# Pressure_Sensor2.net
KiCad netlist of a schematic drawn in EasyEDA
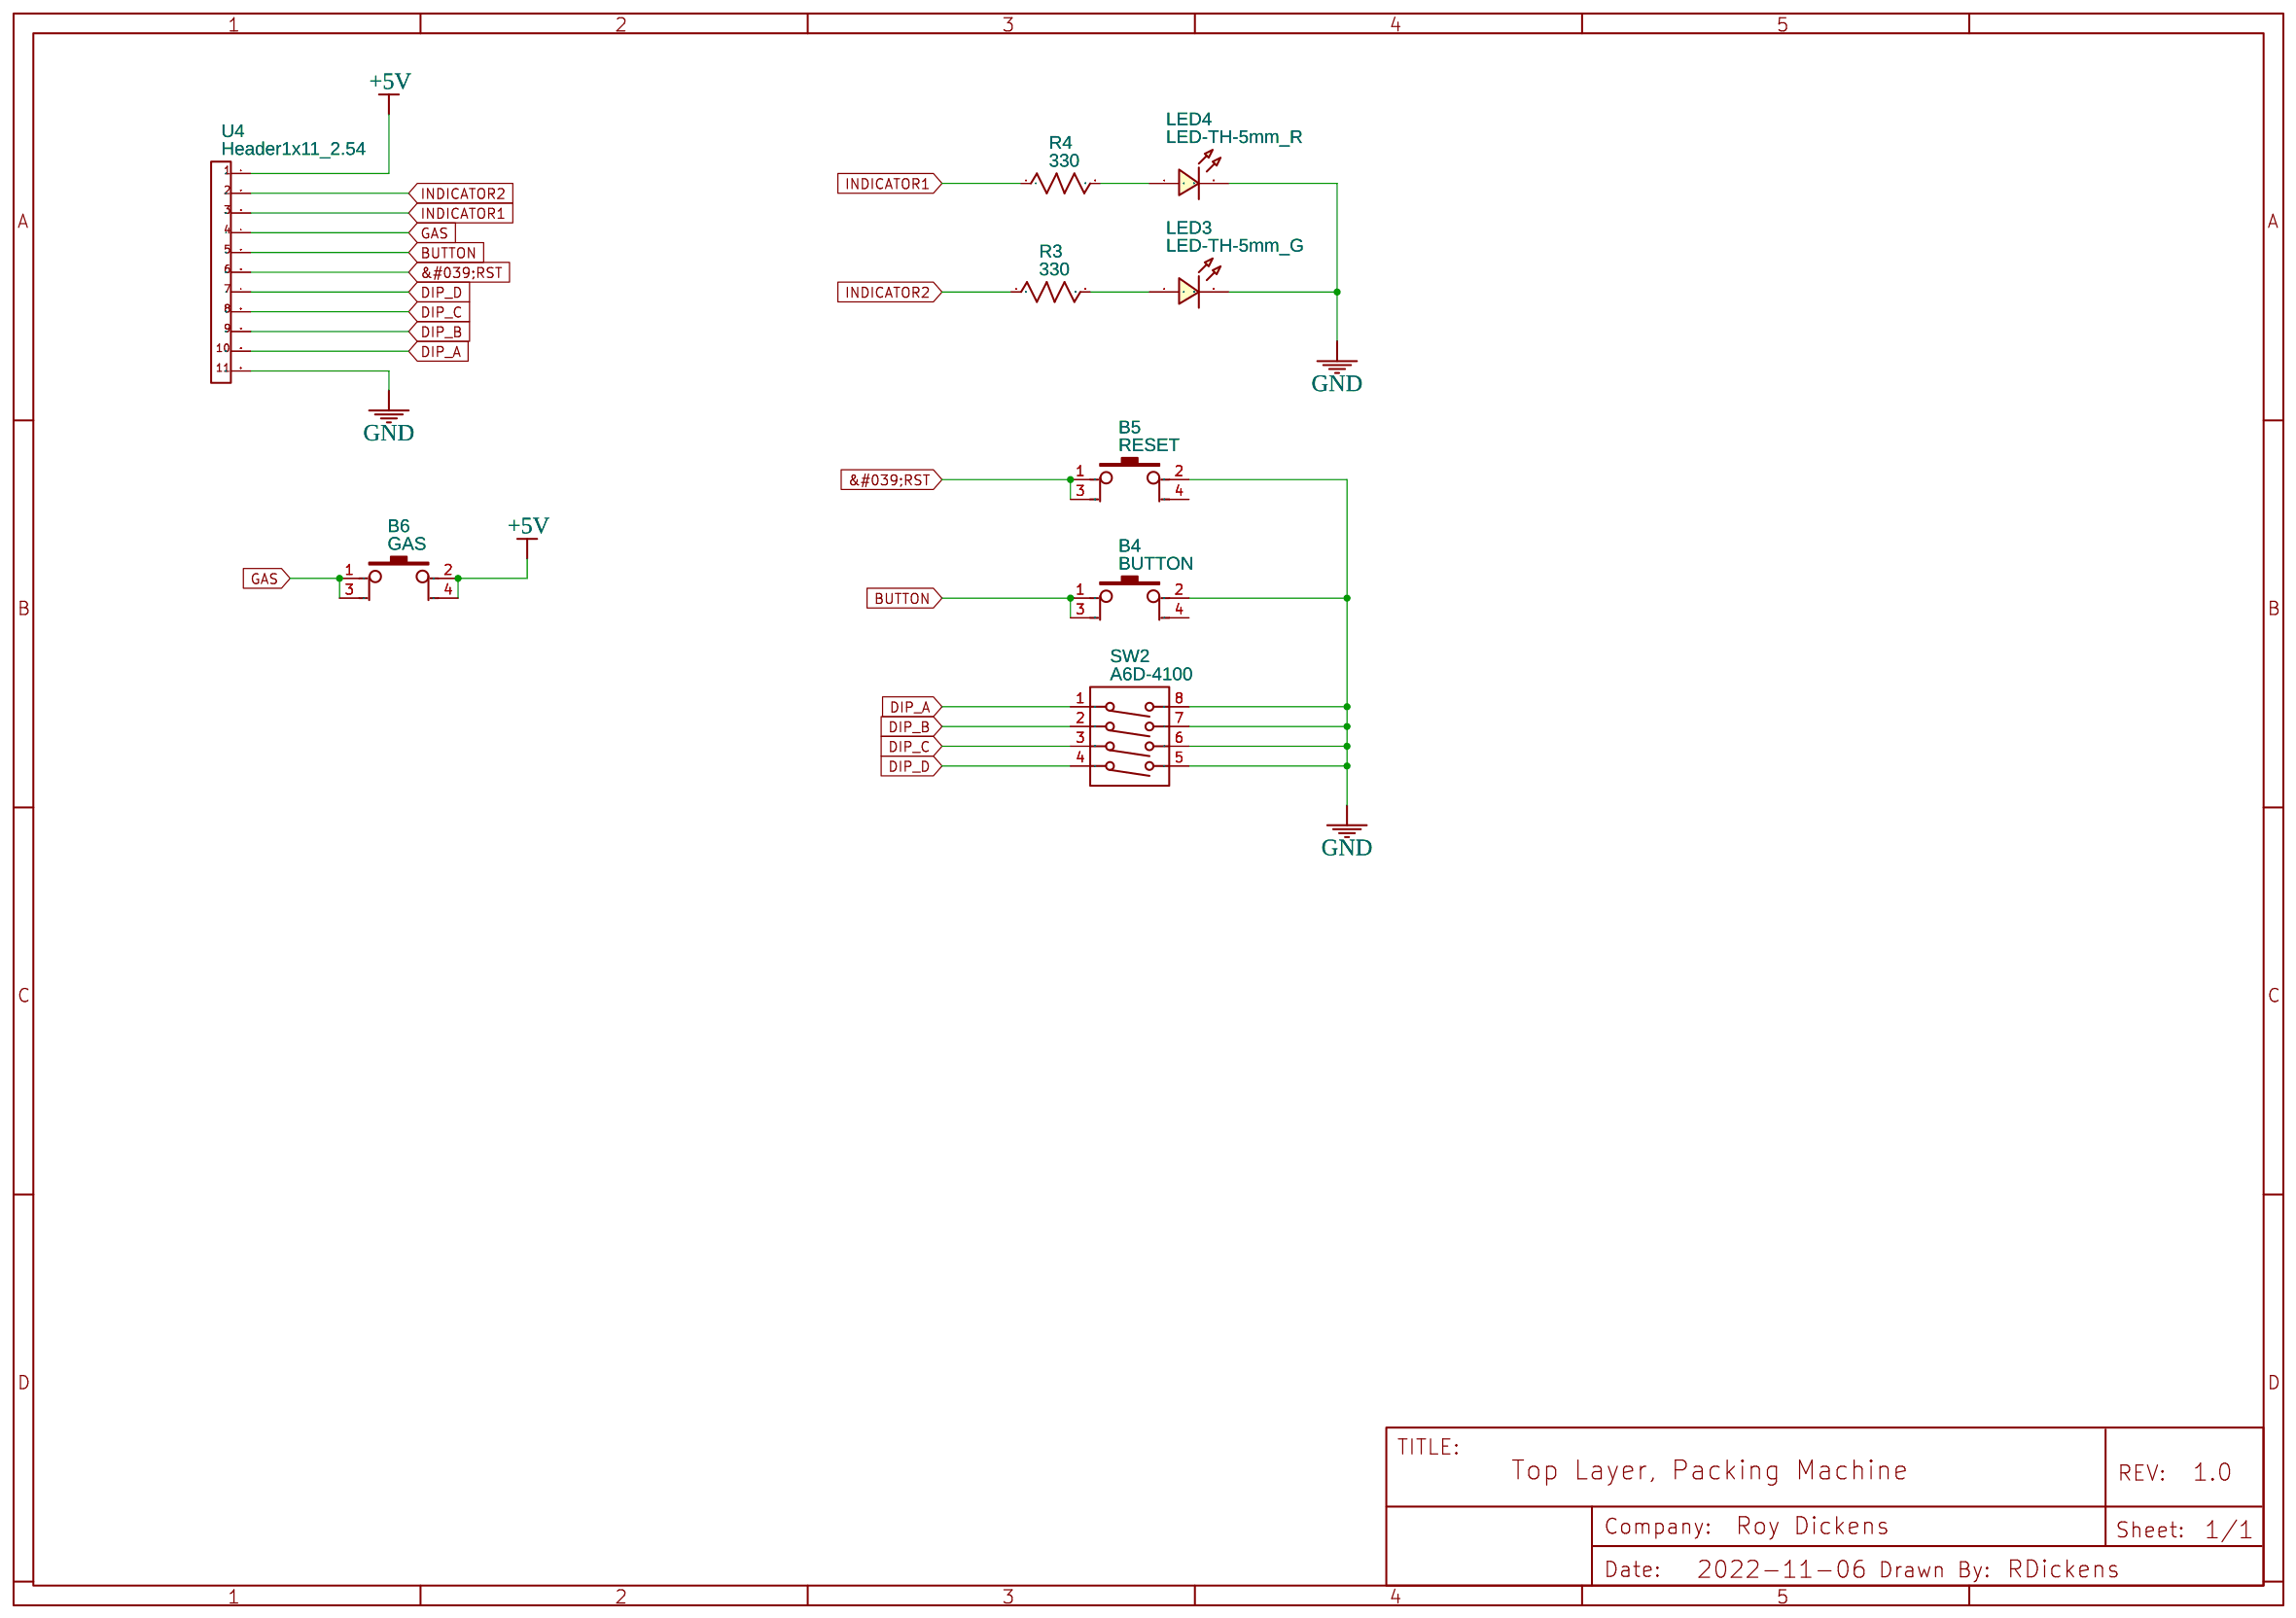
[diagram p0: Sheet_2]
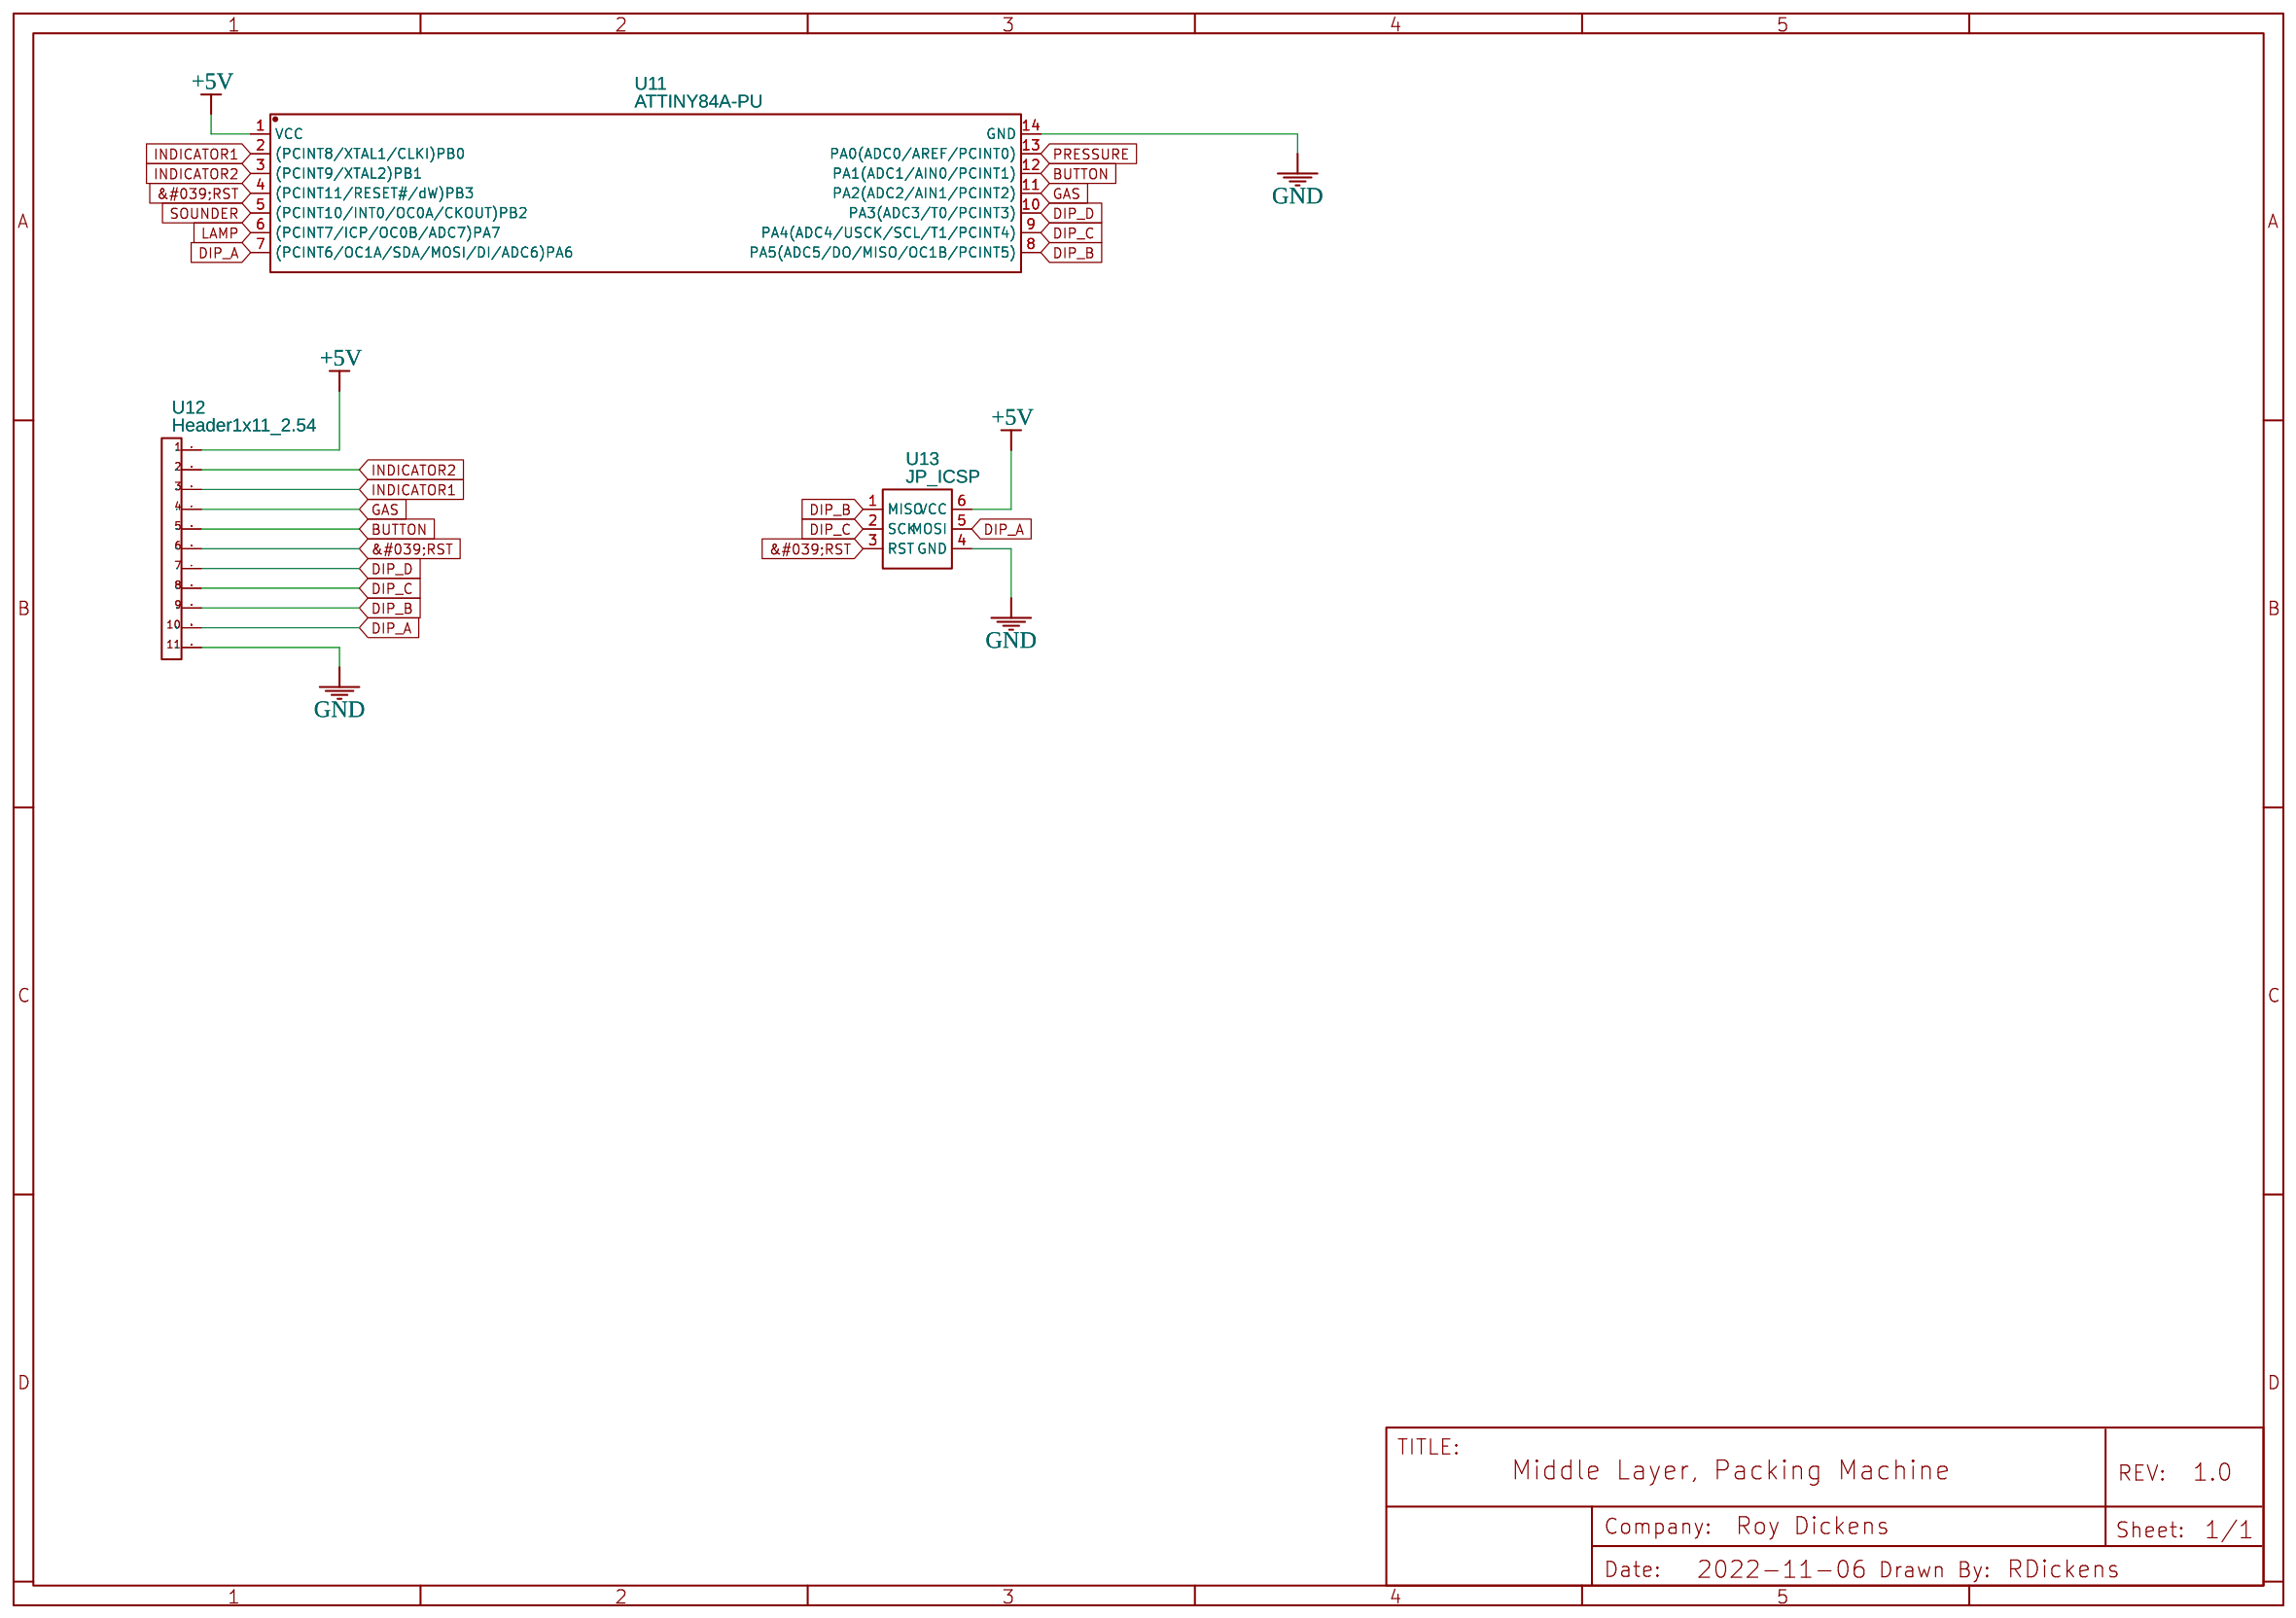
[diagram p1: Sheet_3]
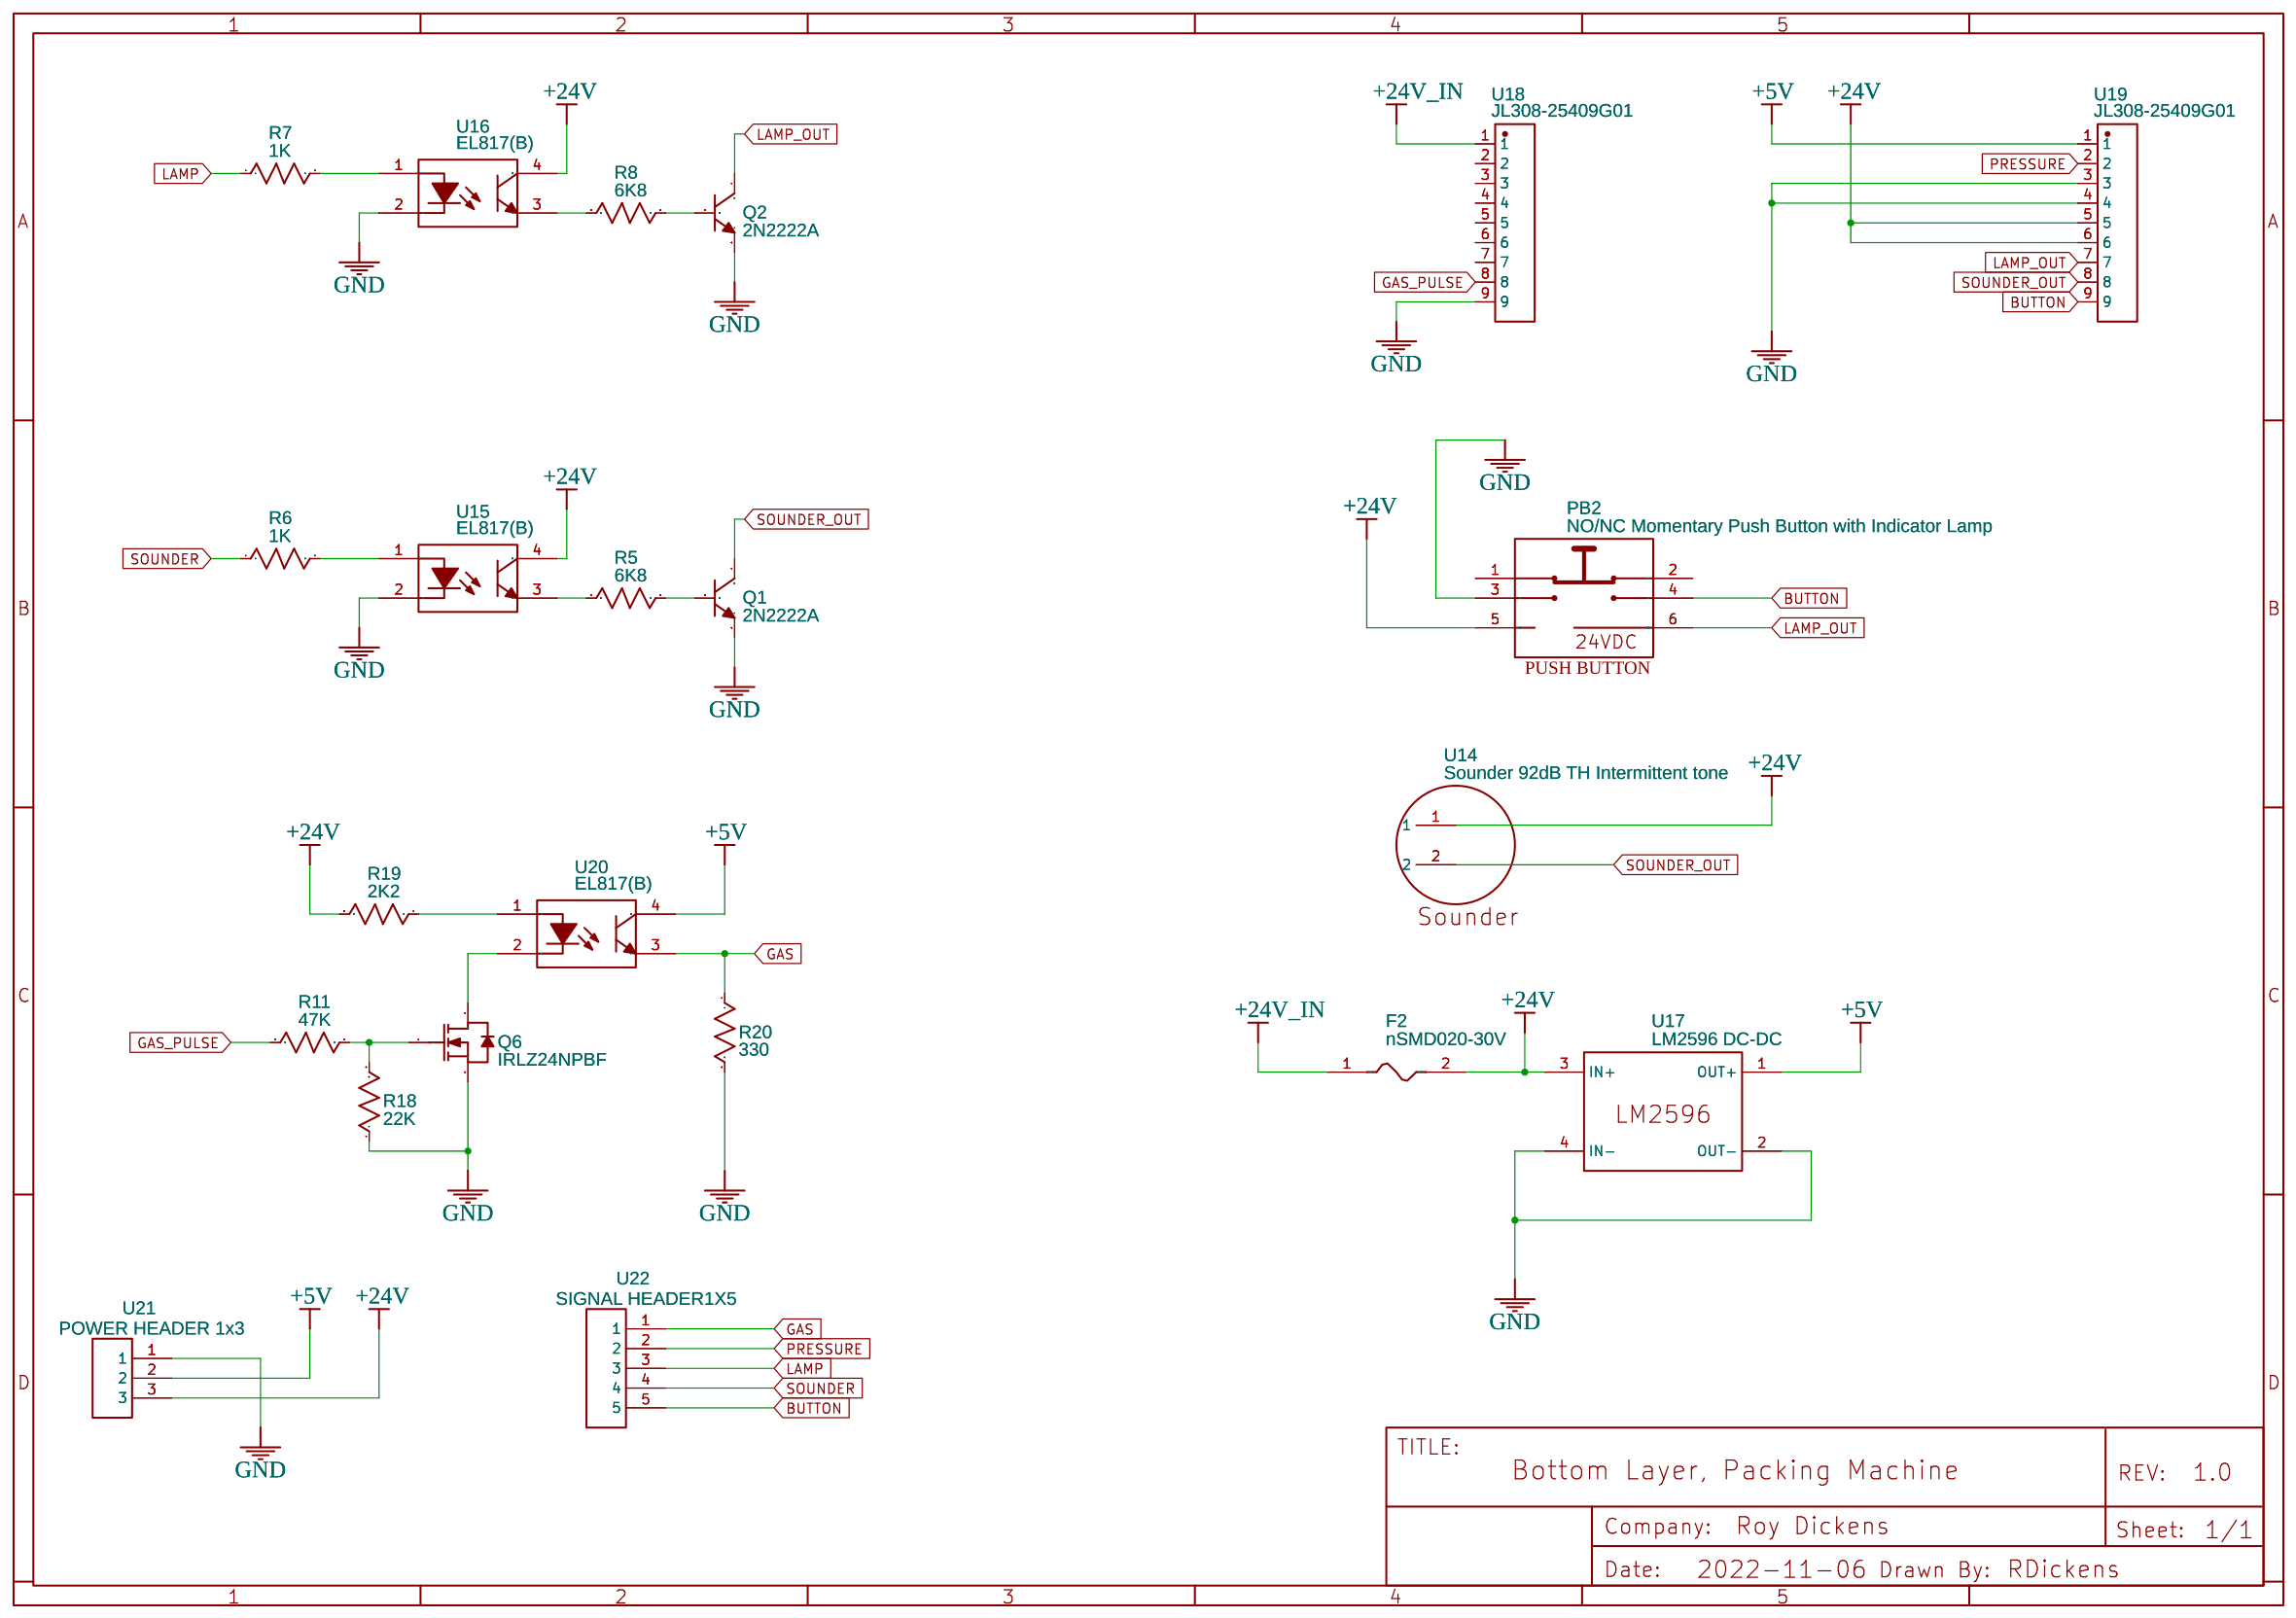
[diagram p2: Sheet_4]

(export (version "E")
  (design (tool "Eeschema 10.0.6"))
  (components
    (comp (ref "B4")
      (value "BUTTON")
      (fields
        (field (name "BOM_Manufacturer Part") "K2-1109DF-F4SW-04")
        (field (name "BOM_Supplier Part") "C2909685")
      )
      (libsource (lib "") (part "PUSHBUTTON"))
    )
    (comp (ref "B5")
      (value "RESET")
      (fields
        (field (name "BOM_Manufacturer Part") "K2-1109DF-F4SW-04")
        (field (name "BOM_Supplier Part") "C2909685")
      )
      (libsource (lib "") (part "PUSHBUTTON"))
    )
    (comp (ref "B6")
      (value "GAS")
      (fields
        (field (name "BOM_Manufacturer Part") "K2-1109DF-F4SW-04")
        (field (name "BOM_Supplier Part") "C2909685")
      )
      (libsource (lib "") (part "PUSHBUTTON"))
    )
    (comp (ref "LED3")
      (value "LED-TH-5mm_G")
      (fields
        (field (name "BOM_Manufacturer Part") "333-2SURD/S530-A3")
        (field (name "BOM_Supplier Part") "C87271")
      )
      (libsource (lib "") (part "LED-TH-5mm_R"))
    )
    (comp (ref "LED4")
      (value "LED-TH-5mm_R")
      (fields
        (field (name "BOM_Manufacturer Part") "333-2SURD/S530-A3")
        (field (name "BOM_Supplier Part") "C87271")
      )
      (libsource (lib "") (part "LED-TH-5mm_R"))
    )
    (comp (ref "R3")
      (value "330")
      (fields
        (field (name "BOM_Manufacturer Part") "MF1/4W-330Ω±1%T52")
        (field (name "BOM_Supplier Part") "C713986")
      )
      (libsource (lib "") (part "R_0603_US"))
    )
    (comp (ref "R4")
      (value "330")
      (fields
        (field (name "BOM_Manufacturer Part") "MF1/4W-330Ω±1%T52")
        (field (name "BOM_Supplier Part") "C713986")
      )
      (libsource (lib "") (part "R_0603_US"))
    )
    (comp (ref "SW2")
      (value "A6D-4100")
      (fields (field (name "BOM_Supplier Part") "C3313543"))
      (libsource (lib "") (part "A6D-4100"))
    )
    (comp (ref "U4") (value "Header1x11_2.54") (libsource (lib "") (part "Header1x11_2.54")))
    (comp (ref "U11")
      (value "ATTINY84A-PU")
      (fields (field (name "BOM_Supplier Part") "C145560"))
      (libsource (lib "") (part "ATTINY84A-PU"))
    )
    (comp (ref "U12") (value "Header1x11_2.54") (libsource (lib "") (part "Header1x11_2.54")))
    (comp (ref "U13")
      (value "JP_ICSP")
      (fields
        (field (name "BOM_Manufacturer Part") "321006SG0ABK00A01")
        (field (name "BOM_Supplier Part") "C601936")
      )
      (libsource (lib "") (part "JP_ICSP"))
    )
    (comp (ref "F2")
      (value "nSMD020-30V")
      (fields (field (name "BOM_Supplier Part") "C69680"))
      (libsource (lib "") (part "nSMD020-30V"))
    )
    (comp (ref "PB2")
      (value "NO/NC Momentary Push Button with Indicator Lamp")
      (libsource (lib "") (part "NO/NC Momentary Push Button with Indicator Lamp"))
    )
    (comp (ref "Q1")
      (value "2N2222A")
      (fields (field (name "BOM_Supplier Part") "C358533"))
      (libsource (lib "") (part "2N2222A"))
    )
    (comp (ref "Q2")
      (value "2N2222A")
      (fields (field (name "BOM_Supplier Part") "C358533"))
      (libsource (lib "") (part "2N2222A"))
    )
    (comp (ref "Q6")
      (value "IRLZ24NPBF")
      (fields (field (name "BOM_Supplier Part") "C11733"))
      (libsource (lib "") (part "IRLZ24NPBF"))
    )
    (comp (ref "R5")
      (value "6K8")
      (fields (field (name "BOM_Supplier Part") "C119314"))
      (libsource (lib "") (part "R_0603_US_1"))
    )
    (comp (ref "R6")
      (value "1K")
      (fields (field (name "BOM_Supplier Part") "C119314"))
      (libsource (lib "") (part "R_0603_US"))
    )
    (comp (ref "R7")
      (value "1K")
      (fields (field (name "BOM_Supplier Part") "C119314"))
      (libsource (lib "") (part "R_0603_US"))
    )
    (comp (ref "R8")
      (value "6K8")
      (fields (field (name "BOM_Supplier Part") "C119314"))
      (libsource (lib "") (part "R_0603_US_1"))
    )
    (comp (ref "R11")
      (value "47K")
      (fields
        (field (name "BOM_Manufacturer Part") "MF1/4W-24KΩ±1%T52")
        (field (name "BOM_Supplier Part") "C714023")
      )
      (libsource (lib "") (part "R_0603_US"))
    )
    (comp (ref "R18")
      (value "22K")
      (fields
        (field (name "BOM_Manufacturer Part") "MF1/4W-24KΩ±1%T52")
        (field (name "BOM_Supplier Part") "C714023")
      )
      (libsource (lib "") (part "R_0603_US_3"))
    )
    (comp (ref "R19")
      (value "2K2")
      (fields
        (field (name "BOM_Manufacturer Part") "MF1/4W-2.2KΩ±1%T52")
        (field (name "BOM_Supplier Part") "C714002")
      )
      (libsource (lib "") (part "R_0603_US_1"))
    )
    (comp (ref "R20")
      (value "330")
      (fields (field (name "BOM_Supplier Part") "C119314"))
      (libsource (lib "") (part "R_0603_US_2"))
    )
    (comp (ref "U14")
      (value "Sounder 92dB TH Intermittent tone")
      (fields (field (name "BOM_Supplier Part") "172-7560"))
      (libsource (lib "") (part "Sounder 92dB TH Intermittent tone"))
    )
    (comp (ref "U15")
      (value "EL817(B)")
      (fields (field (name "BOM_Supplier Part") "C4749156"))
      (libsource (lib "") (part "EL817(B)"))
    )
    (comp (ref "U16")
      (value "EL817(B)")
      (fields (field (name "BOM_Supplier Part") "C4749156"))
      (libsource (lib "") (part "EL817(B)"))
    )
    (comp (ref "U17") (value "LM2596 DC-DC") (libsource (lib "") (part "LM2596 DC-DC")))
    (comp (ref "U18")
      (value "JL308-25409G01")
      (fields (field (name "BOM_Supplier Part") "C99418"))
      (libsource (lib "") (part "JL308-25409G01"))
    )
    (comp (ref "U19")
      (value "JL308-25409G01")
      (fields (field (name "BOM_Supplier Part") "C99418"))
      (libsource (lib "") (part "JL308-25409G01"))
    )
    (comp (ref "U20")
      (value "EL817(B)")
      (fields (field (name "BOM_Supplier Part") "C4749156"))
      (libsource (lib "") (part "EL817(B)"))
    )
    (comp (ref "U21")
      (value "POWER HEADER 1x3")
      (fields (field (name "BOM_Manufacturer Part") "Pin_Header_2"))
      (libsource (lib "") (part "PINHEADER1X3"))
    )
    (comp (ref "U22")
      (value "SIGNAL HEADER1X5")
      (fields (field (name "BOM_Supplier Part") "undefined"))
      (libsource (lib "") (part "PINHEADER1X5"))
    )
  )
  (nets
    (net (code "1") (name "&#039;RST") (class "Default")
      (node (ref "B5") (pin "1") (pinfunction "1_1") (pintype "input"))
      (node (ref "B5") (pin "3") (pinfunction "3_3") (pintype "input"))
      (node (ref "U11") (pin "4") (pinfunction "(PCINT11/RESET#/dW)PB3_4") (pintype "unspecified"))
      (node (ref "U12") (pin "6") (pinfunction "6_6") (pintype "unspecified"))
      (node (ref "U13") (pin "3") (pinfunction "RST_3") (pintype "unspecified"))
      (node (ref "U4") (pin "6") (pinfunction "6_6") (pintype "unspecified"))
    )
    (net (code "2") (name "+5V") (class "Default")
      (node (ref "B6") (pin "2") (pinfunction "3_2") (pintype "input"))
      (node (ref "B6") (pin "4") (pinfunction "4_4") (pintype "input"))
      (node (ref "U11") (pin "1") (pinfunction "VCC_1") (pintype "unspecified"))
      (node (ref "U12") (pin "1") (pinfunction "1_1") (pintype "unspecified"))
      (node (ref "U13") (pin "6") (pinfunction "VCC_6") (pintype "unspecified"))
      (node (ref "U17") (pin "1") (pinfunction "OUT+_1") (pintype "unspecified"))
      (node (ref "U19") (pin "1") (pinfunction "1_1") (pintype "unspecified"))
      (node (ref "U20") (pin "4") (pinfunction "C_4") (pintype "unspecified"))
      (node (ref "U21") (pin "2") (pinfunction "2_2") (pintype "unspecified"))
      (node (ref "U4") (pin "1") (pinfunction "1_1") (pintype "unspecified"))
    )
    (net (code "3") (name "+24V") (class "Default")
      (node (ref "F2") (pin "2") (pinfunction "2_2") (pintype "unspecified"))
      (node (ref "PB2") (pin "5") (pinfunction "LED_5") (pintype "passive"))
      (node (ref "R19") (pin "2") (pinfunction "2_2") (pintype "unspecified"))
      (node (ref "U14") (pin "1") (pinfunction "1_1") (pintype "unspecified"))
      (node (ref "U15") (pin "4") (pinfunction "C_4") (pintype "unspecified"))
      (node (ref "U16") (pin "4") (pinfunction "C_4") (pintype "unspecified"))
      (node (ref "U17") (pin "3") (pinfunction "IN+_3") (pintype "unspecified"))
      (node (ref "U19") (pin "5") (pinfunction "5_5") (pintype "unspecified"))
      (node (ref "U19") (pin "6") (pinfunction "6_6") (pintype "unspecified"))
      (node (ref "U21") (pin "3") (pinfunction "3_3") (pintype "unspecified"))
    )
    (net (code "4") (name "+24V_IN") (class "Default")
      (node (ref "F2") (pin "1") (pinfunction "1_1") (pintype "unspecified"))
      (node (ref "U18") (pin "1") (pinfunction "1_1") (pintype "unspecified"))
    )
    (net (code "5") (name "BUTTON") (class "Default")
      (node (ref "B4") (pin "1") (pinfunction "1_1") (pintype "input"))
      (node (ref "B4") (pin "3") (pinfunction "3_3") (pintype "input"))
      (node (ref "PB2") (pin "4") (pinfunction "NO_4") (pintype "passive"))
      (node (ref "U11") (pin "12") (pinfunction "PA1(ADC1/AIN0/PCINT1)_12") (pintype "unspecified"))
      (node (ref "U12") (pin "5") (pinfunction "5_5") (pintype "unspecified"))
      (node (ref "U19") (pin "9") (pinfunction "9_9") (pintype "unspecified"))
      (node (ref "U22") (pin "5") (pinfunction "5_5") (pintype "unspecified"))
      (node (ref "U4") (pin "5") (pinfunction "5_5") (pintype "unspecified"))
    )
    (net (code "6") (name "DIP_A") (class "Default")
      (node (ref "SW2") (pin "1") (pinfunction "1_1") (pintype "unspecified"))
      (node (ref "U11") (pin "7") (pinfunction "(PCINT6/OC1A/SDA/MOSI/DI/ADC6)PA6_7") (pintype "unspecified"))
      (node (ref "U12") (pin "10") (pinfunction "10_10") (pintype "unspecified"))
      (node (ref "U13") (pin "5") (pinfunction "MOSI_5") (pintype "unspecified"))
      (node (ref "U4") (pin "10") (pinfunction "10_10") (pintype "unspecified"))
    )
    (net (code "7") (name "DIP_B") (class "Default")
      (node (ref "SW2") (pin "2") (pinfunction "2_2") (pintype "unspecified"))
      (node (ref "U11") (pin "8") (pinfunction "PA5(ADC5/DO/MISO/OC1B/PCINT5)_8") (pintype "unspecified"))
      (node (ref "U12") (pin "9") (pinfunction "9_9") (pintype "unspecified"))
      (node (ref "U13") (pin "1") (pinfunction "MISO_1") (pintype "unspecified"))
      (node (ref "U4") (pin "9") (pinfunction "9_9") (pintype "unspecified"))
    )
    (net (code "8") (name "DIP_C") (class "Default")
      (node (ref "SW2") (pin "3") (pinfunction "3_3") (pintype "unspecified"))
      (node (ref "U11") (pin "9") (pinfunction "PA4(ADC4/USCK/SCL/T1/PCINT4)_9") (pintype "unspecified"))
      (node (ref "U12") (pin "8") (pinfunction "8_8") (pintype "unspecified"))
      (node (ref "U13") (pin "2") (pinfunction "SCK_2") (pintype "unspecified"))
      (node (ref "U4") (pin "8") (pinfunction "8_8") (pintype "unspecified"))
    )
    (net (code "9") (name "DIP_D") (class "Default")
      (node (ref "SW2") (pin "4") (pinfunction "4_4") (pintype "unspecified"))
      (node (ref "U11") (pin "10") (pinfunction "PA3(ADC3/T0/PCINT3)_10") (pintype "unspecified"))
      (node (ref "U12") (pin "7") (pinfunction "7_7") (pintype "unspecified"))
      (node (ref "U4") (pin "7") (pinfunction "7_7") (pintype "unspecified"))
    )
    (net (code "10") (name "GAS") (class "Default")
      (node (ref "B6") (pin "1") (pinfunction "1_1") (pintype "input"))
      (node (ref "B6") (pin "3") (pinfunction "3_3") (pintype "input"))
      (node (ref "R20") (pin "1") (pinfunction "1_1") (pintype "unspecified"))
      (node (ref "U11") (pin "11") (pinfunction "PA2(ADC2/AIN1/PCINT2)_11") (pintype "unspecified"))
      (node (ref "U12") (pin "4") (pinfunction "4_4") (pintype "unspecified"))
      (node (ref "U20") (pin "3") (pinfunction "E_3") (pintype "unspecified"))
      (node (ref "U22") (pin "1") (pinfunction "1_1") (pintype "unspecified"))
      (node (ref "U4") (pin "4") (pinfunction "4_4") (pintype "unspecified"))
    )
    (net (code "11") (name "GAS_PULSE") (class "Default")
      (node (ref "R11") (pin "1") (pinfunction "1_1") (pintype "unspecified"))
      (node (ref "U18") (pin "8") (pinfunction "8_8") (pintype "unspecified"))
    )
    (net (code "12") (name "GND") (class "Default")
      (node (ref "B4") (pin "2") (pinfunction "3_2") (pintype "input"))
      (node (ref "B5") (pin "2") (pinfunction "3_2") (pintype "input"))
      (node (ref "LED3") (pin "2") (pinfunction "2_2") (pintype "unspecified"))
      (node (ref "LED4") (pin "2") (pinfunction "2_2") (pintype "unspecified"))
      (node (ref "PB2") (pin "3") (pinfunction "NO_3") (pintype "passive"))
      (node (ref "Q1") (pin "3") (pinfunction "E_3") (pintype "unspecified"))
      (node (ref "Q2") (pin "3") (pinfunction "E_3") (pintype "unspecified"))
      (node (ref "Q6") (pin "3") (pinfunction "S_3") (pintype "unspecified"))
      (node (ref "R18") (pin "1") (pinfunction "1_1") (pintype "unspecified"))
      (node (ref "R20") (pin "2") (pinfunction "2_2") (pintype "unspecified"))
      (node (ref "SW2") (pin "5") (pinfunction "5_5") (pintype "unspecified"))
      (node (ref "SW2") (pin "6") (pinfunction "6_6") (pintype "unspecified"))
      (node (ref "SW2") (pin "7") (pinfunction "7_7") (pintype "unspecified"))
      (node (ref "SW2") (pin "8") (pinfunction "8_8") (pintype "unspecified"))
      (node (ref "U11") (pin "14") (pinfunction "GND_14") (pintype "unspecified"))
      (node (ref "U12") (pin "11") (pinfunction "11_11") (pintype "unspecified"))
      (node (ref "U13") (pin "4") (pinfunction "GND_4") (pintype "unspecified"))
      (node (ref "U15") (pin "2") (pinfunction "C_2") (pintype "unspecified"))
      (node (ref "U16") (pin "2") (pinfunction "C_2") (pintype "unspecified"))
      (node (ref "U17") (pin "2") (pinfunction "OUT-_2") (pintype "unspecified"))
      (node (ref "U17") (pin "4") (pinfunction "IN-_4") (pintype "unspecified"))
      (node (ref "U18") (pin "9") (pinfunction "9_9") (pintype "unspecified"))
      (node (ref "U19") (pin "3") (pinfunction "3_3") (pintype "unspecified"))
      (node (ref "U19") (pin "4") (pinfunction "4_4") (pintype "unspecified"))
      (node (ref "U21") (pin "1") (pinfunction "1_1") (pintype "unspecified"))
      (node (ref "U4") (pin "11") (pinfunction "11_11") (pintype "unspecified"))
    )
    (net (code "13") (name "INDICATOR1") (class "Default")
      (node (ref "R4") (pin "1") (pinfunction "1_1") (pintype "unspecified"))
      (node (ref "U11") (pin "2") (pinfunction "(PCINT8/XTAL1/CLKI)PB0_2") (pintype "unspecified"))
      (node (ref "U12") (pin "3") (pinfunction "3_3") (pintype "unspecified"))
      (node (ref "U4") (pin "3") (pinfunction "3_3") (pintype "unspecified"))
    )
    (net (code "14") (name "INDICATOR2") (class "Default")
      (node (ref "R3") (pin "1") (pinfunction "1_1") (pintype "unspecified"))
      (node (ref "U11") (pin "3") (pinfunction "(PCINT9/XTAL2)PB1_3") (pintype "unspecified"))
      (node (ref "U12") (pin "2") (pinfunction "2_2") (pintype "unspecified"))
      (node (ref "U4") (pin "2") (pinfunction "2_2") (pintype "unspecified"))
    )
    (net (code "15") (name "LAMP") (class "Default")
      (node (ref "R7") (pin "1") (pinfunction "1_1") (pintype "unspecified"))
      (node (ref "U11") (pin "6") (pinfunction "(PCINT7/ICP/OC0B/ADC7)PA7_6") (pintype "unspecified"))
      (node (ref "U22") (pin "3") (pinfunction "3_3") (pintype "unspecified"))
    )
    (net (code "16") (name "LAMP_OUT") (class "Default")
      (node (ref "PB2") (pin "6") (pinfunction "LED_6") (pintype "passive"))
      (node (ref "Q2") (pin "1") (pinfunction "C_1") (pintype "unspecified"))
      (node (ref "U19") (pin "7") (pinfunction "7_7") (pintype "unspecified"))
    )
    (net (code "17") (name "Net-(LED3-Pad1)") (class "Default")
      (node (ref "LED3") (pin "1") (pinfunction "1_1") (pintype "unspecified"))
      (node (ref "R3") (pin "2") (pinfunction "2_2") (pintype "unspecified"))
    )
    (net (code "18") (name "Net-(LED4-Pad1)") (class "Default")
      (node (ref "LED4") (pin "1") (pinfunction "1_1") (pintype "unspecified"))
      (node (ref "R4") (pin "2") (pinfunction "2_2") (pintype "unspecified"))
    )
    (net (code "19") (name "Net-(Q1-B)") (class "Default")
      (node (ref "Q1") (pin "2") (pinfunction "B_2") (pintype "unspecified"))
      (node (ref "R5") (pin "1") (pinfunction "1_1") (pintype "unspecified"))
    )
    (net (code "20") (name "Net-(Q2-B)") (class "Default")
      (node (ref "Q2") (pin "2") (pinfunction "B_2") (pintype "unspecified"))
      (node (ref "R8") (pin "1") (pinfunction "1_1") (pintype "unspecified"))
    )
    (net (code "21") (name "Net-(Q6-D)") (class "Default")
      (node (ref "Q6") (pin "2") (pinfunction "D_2") (pintype "unspecified"))
      (node (ref "U20") (pin "2") (pinfunction "C_2") (pintype "unspecified"))
    )
    (net (code "22") (name "Net-(Q6-G)") (class "Default")
      (node (ref "Q6") (pin "1") (pinfunction "G_1") (pintype "unspecified"))
      (node (ref "R11") (pin "2") (pinfunction "2_2") (pintype "unspecified"))
      (node (ref "R18") (pin "2") (pinfunction "2_2") (pintype "unspecified"))
    )
    (net (code "23") (name "Net-(U15-A)") (class "Default")
      (node (ref "R6") (pin "2") (pinfunction "2_2") (pintype "unspecified"))
      (node (ref "U15") (pin "1") (pinfunction "A_1") (pintype "unspecified"))
    )
    (net (code "24") (name "Net-(U15-E)") (class "Default")
      (node (ref "R5") (pin "2") (pinfunction "2_2") (pintype "unspecified"))
      (node (ref "U15") (pin "3") (pinfunction "E_3") (pintype "unspecified"))
    )
    (net (code "25") (name "Net-(U16-A)") (class "Default")
      (node (ref "R7") (pin "2") (pinfunction "2_2") (pintype "unspecified"))
      (node (ref "U16") (pin "1") (pinfunction "A_1") (pintype "unspecified"))
    )
    (net (code "26") (name "Net-(U16-E)") (class "Default")
      (node (ref "R8") (pin "2") (pinfunction "2_2") (pintype "unspecified"))
      (node (ref "U16") (pin "3") (pinfunction "E_3") (pintype "unspecified"))
    )
    (net (code "27") (name "Net-(U20-A)") (class "Default")
      (node (ref "R19") (pin "1") (pinfunction "1_1") (pintype "unspecified"))
      (node (ref "U20") (pin "1") (pinfunction "A_1") (pintype "unspecified"))
    )
    (net (code "28") (name "PRESSURE") (class "Default")
      (node (ref "U11") (pin "13") (pinfunction "PA0(ADC0/AREF/PCINT0)_13") (pintype "unspecified"))
      (node (ref "U19") (pin "2") (pinfunction "2_2") (pintype "unspecified"))
      (node (ref "U22") (pin "2") (pinfunction "2_2") (pintype "unspecified"))
    )
    (net (code "29") (name "SOUNDER") (class "Default")
      (node (ref "R6") (pin "1") (pinfunction "1_1") (pintype "unspecified"))
      (node (ref "U11") (pin "5") (pinfunction "(PCINT10/INT0/OC0A/CKOUT)PB2_5") (pintype "unspecified"))
      (node (ref "U22") (pin "4") (pinfunction "4_4") (pintype "unspecified"))
    )
    (net (code "30") (name "SOUNDER_OUT") (class "Default")
      (node (ref "Q1") (pin "1") (pinfunction "C_1") (pintype "unspecified"))
      (node (ref "U14") (pin "2") (pinfunction "2_2") (pintype "unspecified"))
      (node (ref "U19") (pin "8") (pinfunction "8_8") (pintype "unspecified"))
    )
    (net (code "31") (name "unconnected-(B4-Pad4)") (class "Default")
      (node (ref "B4") (pin "4") (pinfunction "4_4") (pintype "input"))
    )
    (net (code "32") (name "unconnected-(B5-Pad4)") (class "Default")
      (node (ref "B5") (pin "4") (pinfunction "4_4") (pintype "input"))
    )
    (net (code "33") (name "unconnected-(PB2-NC-Pad1)") (class "Default")
      (node (ref "PB2") (pin "1") (pinfunction "NC_1") (pintype "passive"))
    )
    (net (code "34") (name "unconnected-(PB2-NC-Pad2)") (class "Default")
      (node (ref "PB2") (pin "2") (pinfunction "NC_2") (pintype "passive"))
    )
    (net (code "35") (name "unconnected-(U18-Pad2)") (class "Default")
      (node (ref "U18") (pin "2") (pinfunction "2_2") (pintype "unspecified"))
    )
    (net (code "36") (name "unconnected-(U18-Pad3)") (class "Default")
      (node (ref "U18") (pin "3") (pinfunction "3_3") (pintype "unspecified"))
    )
    (net (code "37") (name "unconnected-(U18-Pad4)") (class "Default")
      (node (ref "U18") (pin "4") (pinfunction "4_4") (pintype "unspecified"))
    )
    (net (code "38") (name "unconnected-(U18-Pad5)") (class "Default")
      (node (ref "U18") (pin "5") (pinfunction "5_5") (pintype "unspecified"))
    )
    (net (code "39") (name "unconnected-(U18-Pad6)") (class "Default")
      (node (ref "U18") (pin "6") (pinfunction "6_6") (pintype "unspecified"))
    )
    (net (code "40") (name "unconnected-(U18-Pad7)") (class "Default")
      (node (ref "U18") (pin "7") (pinfunction "7_7") (pintype "unspecified"))
    )
  )
)
